# EE311_Example_Boost_Sch.net
KiCad netlist of a schematic drawn in Altium Designer
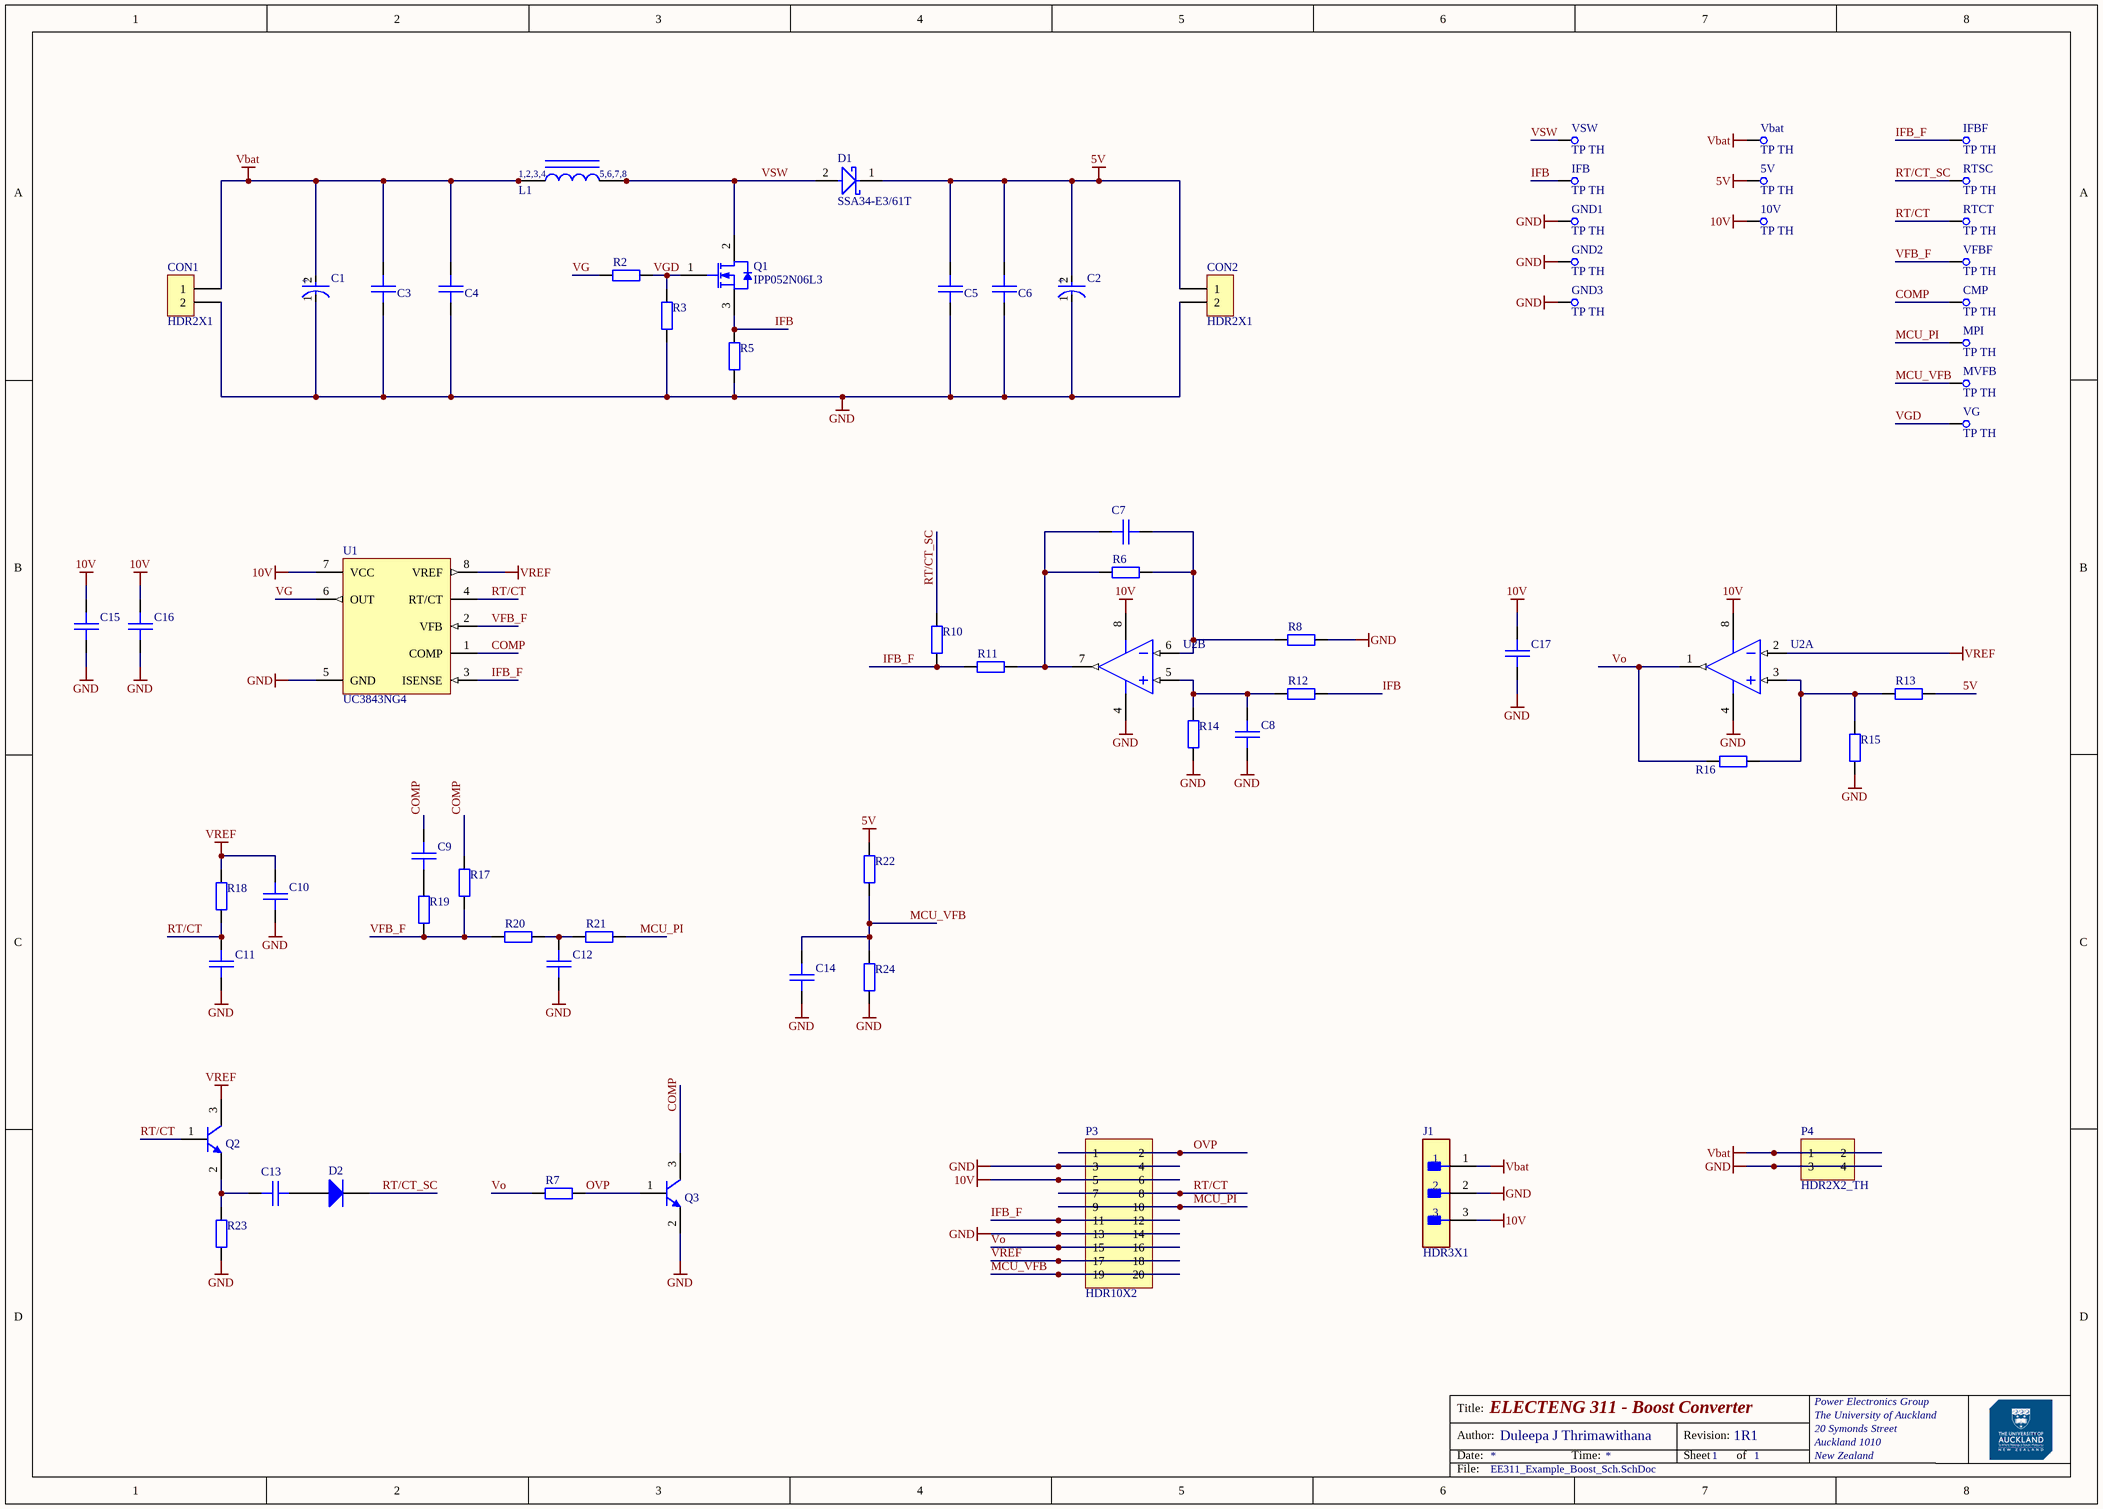
[diagram p0: EE311_Example_Boost_Sch.SchDoc]

(export (version "E")
  (design (tool "Eeschema 10.0.6"))
  (components
    (comp (ref "5V") (value "TP TH") (footprint "TP_TH_2.5mm") (libsource (lib "ECSE@UoA") (part "TP TH")))
    (comp (ref "10V") (value "TP TH") (footprint "TP_TH_2.5mm") (libsource (lib "ECSE@UoA") (part "TP TH")))
    (comp (ref "C1")
      (value "EEE-FK1K330P")
      (footprint "FP-FKF-MFG")
      (libsource (lib "ECSE@UoA") (part "a00bbbee19879c290e62620ae7e47b1"))
    )
    (comp (ref "C2")
      (value "EEE-FK1K330P")
      (footprint "FP-FKF-MFG")
      (libsource (lib "ECSE@UoA") (part "a00bbbee19879c290e62620ae7e47b1"))
    )
    (comp (ref "C3")
      (value "CCAP1210")
      (footprint "C1210")
      (description "Capacitor 1210")
      (libsource (lib "") (part "Symbol_2"))
    )
    (comp (ref "C4")
      (value "CCAP1210")
      (footprint "C1210")
      (description "Capacitor 1210")
      (libsource (lib "") (part "Symbol_2"))
    )
    (comp (ref "C5")
      (value "CCAP1210")
      (footprint "C1210")
      (description "Capacitor 1210")
      (libsource (lib "") (part "Symbol_2"))
    )
    (comp (ref "C6")
      (value "CCAP1210")
      (footprint "C1210")
      (description "Capacitor 1210")
      (libsource (lib "") (part "Symbol_2"))
    )
    (comp (ref "C7")
      (value "CCAP0805")
      (footprint "C0805")
      (description "Capacitor 0805")
      (libsource (lib "") (part "Symbol_2"))
    )
    (comp (ref "C8")
      (value "CCAP0805")
      (footprint "C0805")
      (description "Capacitor 0805")
      (libsource (lib "") (part "Symbol_2"))
    )
    (comp (ref "C9")
      (value "CCAP0805")
      (footprint "C0805")
      (description "Capacitor 0805")
      (libsource (lib "") (part "Symbol_2"))
    )
    (comp (ref "C10")
      (value "CCAP0805")
      (footprint "C0805")
      (description "Capacitor 0805")
      (libsource (lib "") (part "Symbol_2"))
    )
    (comp (ref "C11")
      (value "CCAP0805")
      (footprint "C0805")
      (description "Capacitor 0805")
      (libsource (lib "") (part "Symbol_2"))
    )
    (comp (ref "C12")
      (value "CCAP0805")
      (footprint "C0805")
      (description "Capacitor 0805")
      (libsource (lib "") (part "Symbol_2"))
    )
    (comp (ref "C13")
      (value "CCAP0805")
      (footprint "C0805")
      (description "Capacitor 0805")
      (libsource (lib "") (part "Symbol_2"))
    )
    (comp (ref "C14")
      (value "CCAP0805")
      (footprint "C0805")
      (description "Capacitor 0805")
      (libsource (lib "") (part "Symbol_2"))
    )
    (comp (ref "C15")
      (value "CCAP0805")
      (footprint "C0805")
      (description "Capacitor 0805")
      (libsource (lib "") (part "Symbol_2"))
    )
    (comp (ref "C16")
      (value "CCAP0805")
      (footprint "C0805")
      (description "Capacitor 0805")
      (libsource (lib "") (part "Symbol_2"))
    )
    (comp (ref "C17")
      (value "CCAP0805")
      (footprint "C0805")
      (description "Capacitor 0805")
      (libsource (lib "") (part "Symbol_2"))
    )
    (comp (ref "CMP") (value "TP TH") (footprint "TP_TH_2.5mm") (libsource (lib "ECSE@UoA") (part "TP TH")))
    (comp (ref "CON1")
      (value "HDR2X1")
      (footprint "HDR2X1_2P54")
      (description "Header 2X1")
      (libsource (lib "ECSE@UoA") (part "HDR2X1"))
    )
    (comp (ref "CON2")
      (value "HDR2X1")
      (footprint "HDR2X1_2P54")
      (description "Header 2X1")
      (libsource (lib "") (part "HDR2X1_1"))
    )
    (comp (ref "D1")
      (value "SSA34-E3/61T")
      (footprint "FP-95400-MFG")
      (description "Rectifier Diode, Schottky, 1 Phase, 1 Element, 3A, 40V V(RRM), Silicon, DO-214AC")
      (libsource (lib "ECSE@UoA") (part "1d6ec82d83fb6aee721767c19dac4b9"))
    )
    (comp (ref "D2")
      (value "1N4148_SMT_SOD123")
      (footprint "SOD123")
      (description "DIODE GEN PURP 100V 300MA SOD123")
      (fields
        (field (name "MANUFACTURER PART NUMBER") "1N4148W-13-F")
        (field (name "BASE PART NUMBER") "1N4148W")
      )
      (libsource (lib "ECSE@UoA") (part "1N4148_SMT_SOD123"))
    )
    (comp (ref "GND1") (value "TP TH") (footprint "TP_TH_3mm") (libsource (lib "ECSE@UoA") (part "TP TH")))
    (comp (ref "GND2") (value "TP TH") (footprint "TP_TH_3mm") (libsource (lib "ECSE@UoA") (part "TP TH")))
    (comp (ref "GND3") (value "TP TH") (footprint "TP_TH_3mm") (libsource (lib "ECSE@UoA") (part "TP TH")))
    (comp (ref "IFB") (value "TP TH") (footprint "TP_TH_3mm") (libsource (lib "ECSE@UoA") (part "TP TH")))
    (comp (ref "IFBF") (value "TP TH") (footprint "TP_TH_2.5mm") (libsource (lib "ECSE@UoA") (part "TP TH")))
    (comp (ref "J1")
      (value "HDR3X1")
      (footprint "FP-22-28-4035-MFG")
      (libsource (lib "ECSE@UoA") (part "0d3f023dd272f625e17a2be33dea85f"))
    )
    (comp (ref "L1")
      (value "Inductor EFD20")
      (footprint "EFD20")
      (description "Inductor with core")
      (libsource (lib "ECSE@UoA") (part "Inductor EFD20"))
    )
    (comp (ref "MPI") (value "TP TH") (footprint "TP_TH_2.5mm") (libsource (lib "ECSE@UoA") (part "TP TH")))
    (comp (ref "MVFB") (value "TP TH") (footprint "TP_TH_2.5mm") (libsource (lib "ECSE@UoA") (part "TP TH")))
    (comp (ref "P3")
      (value "HDR10X2")
      (footprint "HDR10X2_2P54")
      (description "Header, 10-Pin, Dual row")
      (libsource (lib "ECSE@UoA") (part "HDR10X2"))
    )
    (comp (ref "P4")
      (value "HDR2X2_TH")
      (footprint "HDR2X2_2P54_Male")
      (description "Male Header, 4-Pin, Dual row")
      (libsource (lib "ECSE@UoA") (part "HDR2X2"))
    )
    (comp (ref "Q1")
      (value "IPP052N06L3")
      (footprint "TO220VH")
      (fields (field (name "MANUFACTURER") "Infineon") (field (name "PARTNUMBER") "IPP052N06L3 G"))
      (libsource (lib "ECSE@UoA") (part "IPP052N06L3"))
    )
    (comp (ref "Q2")
      (value "MMBT2222A")
      (footprint "SOT23SM")
      (description "General Purpose Transistor, NPN Silicon, 3-Pin SOT-23, Pb-Free, Tape and Reel")
      (fields (field (name "PARTNUMBER") "MMBT2222ALT1G") (field (name "MANUFACTURER") "On Semiconductor"))
      (libsource (lib "ECSE@UoA") (part "MMBT2222A"))
    )
    (comp (ref "Q3")
      (value "MMBT2222A")
      (footprint "SOT23SM")
      (description "General Purpose Transistor, NPN Silicon, 3-Pin SOT-23, Pb-Free, Tape and Reel")
      (fields (field (name "PARTNUMBER") "MMBT2222ALT1G") (field (name "MANUFACTURER") "On Semiconductor"))
      (libsource (lib "ECSE@UoA") (part "MMBT2222A"))
    )
    (comp (ref "R2")
      (value "RES0805")
      (footprint "R0805")
      (description "Resistor 0805")
      (libsource (lib "ECSE@UoA") (part "Symbol"))
    )
    (comp (ref "R3")
      (value "RES0805")
      (footprint "R0805")
      (description "Resistor 0805")
      (libsource (lib "") (part "Symbol_1"))
    )
    (comp (ref "R5")
      (value "RES1210")
      (footprint "R1210")
      (description "Resistor 1210")
      (libsource (lib "") (part "Symbol_1"))
    )
    (comp (ref "R6")
      (value "RES0805")
      (footprint "R0805")
      (description "Resistor 0805")
      (libsource (lib "") (part "Symbol_1"))
    )
    (comp (ref "R7")
      (value "RES0805")
      (footprint "R0805")
      (description "Resistor 0805")
      (libsource (lib "") (part "Symbol_1"))
    )
    (comp (ref "R8")
      (value "RES0805")
      (footprint "R0805")
      (description "Resistor 0805")
      (libsource (lib "") (part "Symbol_1"))
    )
    (comp (ref "R10")
      (value "RES0805")
      (footprint "R0805")
      (description "Resistor 0805")
      (libsource (lib "") (part "Symbol_3"))
    )
    (comp (ref "R11")
      (value "RES0805")
      (footprint "R0805")
      (description "Resistor 0805")
      (libsource (lib "") (part "Symbol_1"))
    )
    (comp (ref "R12")
      (value "RES0805")
      (footprint "R0805")
      (description "Resistor 0805")
      (libsource (lib "") (part "Symbol_1"))
    )
    (comp (ref "R13")
      (value "RES0805")
      (footprint "R0805")
      (description "Resistor 0805")
      (libsource (lib "") (part "Symbol_1"))
    )
    (comp (ref "R14")
      (value "RES0805")
      (footprint "R0805")
      (description "Resistor 0805")
      (libsource (lib "ECSE@UoA") (part "Symbol"))
    )
    (comp (ref "R15")
      (value "RES0805")
      (footprint "R0805")
      (description "Resistor 0805")
      (libsource (lib "ECSE@UoA") (part "Symbol"))
    )
    (comp (ref "R16")
      (value "RES0805")
      (footprint "R0805")
      (description "Resistor 0805")
      (libsource (lib "") (part "Symbol_1"))
    )
    (comp (ref "R17")
      (value "RES0805")
      (footprint "R0805")
      (description "Resistor 0805")
      (libsource (lib "") (part "Symbol_1"))
    )
    (comp (ref "R18")
      (value "RES0805")
      (footprint "R0805")
      (description "Resistor 0805")
      (libsource (lib "") (part "Symbol_1"))
    )
    (comp (ref "R19")
      (value "RES0805")
      (footprint "R0805")
      (description "Resistor 0805")
      (libsource (lib "") (part "Symbol_1"))
    )
    (comp (ref "R20")
      (value "RES0805")
      (footprint "R0805")
      (description "Resistor 0805")
      (libsource (lib "") (part "Symbol_3"))
    )
    (comp (ref "R21")
      (value "RES0805")
      (footprint "R0805")
      (description "Resistor 0805")
      (libsource (lib "") (part "Symbol_3"))
    )
    (comp (ref "R22")
      (value "RES0805")
      (footprint "R0805")
      (description "Resistor 0805")
      (libsource (lib "") (part "Symbol_1"))
    )
    (comp (ref "R23")
      (value "RES0805")
      (footprint "R0805")
      (description "Resistor 0805")
      (libsource (lib "") (part "Symbol_3"))
    )
    (comp (ref "R24")
      (value "RES0805")
      (footprint "R0805")
      (description "Resistor 0805")
      (libsource (lib "") (part "Symbol_1"))
    )
    (comp (ref "RTCT") (value "TP TH") (footprint "TP_TH_2.5mm") (libsource (lib "ECSE@UoA") (part "TP TH")))
    (comp (ref "RTSC") (value "TP TH") (footprint "TP_TH_2.5mm") (libsource (lib "ECSE@UoA") (part "TP TH")))
    (comp (ref "U1")
      (value "UC3843NG4")
      (footprint "DIP-8")
      (libsource (lib "ECSE@UoA") (part "TI-UC3843P8"))
    )
    (comp (ref "U2")
      (value "LT6221")
      (footprint "SOIC8")
      (description "IC OPAMP LT6221 DUAL SM")
      (libsource (lib "ECSE@UoA") (part "LT6221"))
    )
    (comp (ref "Vbat") (value "TP TH") (footprint "TP_TH_2.5mm") (libsource (lib "ECSE@UoA") (part "TP TH")))
    (comp (ref "VFBF") (value "TP TH") (footprint "TP_TH_2.5mm") (libsource (lib "ECSE@UoA") (part "TP TH")))
    (comp (ref "VG") (value "TP TH") (footprint "TP_TH_2.5mm") (libsource (lib "ECSE@UoA") (part "TP TH")))
    (comp (ref "VSW") (value "TP TH") (footprint "TP_TH_3mm") (libsource (lib "ECSE@UoA") (part "TP TH")))
  )
  (nets
    (net (code "1") (name "/COMP") (class "Default")
      (node (ref "C9") (pin "1") (pinfunction "1_1") (pintype "passive"))
      (node (ref "CMP") (pin "1") (pinfunction "1_1") (pintype "passive"))
      (node (ref "Q3") (pin "3") (pinfunction "C_3") (pintype "passive"))
      (node (ref "R17") (pin "2") (pinfunction "2_2") (pintype "passive"))
      (node (ref "U1") (pin "1") (pinfunction "COMP_1") (pintype "passive"))
    )
    (net (code "2") (name "/IFB") (class "Default")
      (node (ref "IFB") (pin "1") (pinfunction "1_1") (pintype "passive"))
      (node (ref "Q1") (pin "3") (pinfunction "SOURCE_3") (pintype "passive"))
      (node (ref "R12") (pin "2") (pinfunction "2_2") (pintype "passive"))
      (node (ref "R5") (pin "2") (pinfunction "2_2") (pintype "passive"))
    )
    (net (code "3") (name "/IFB_F") (class "Default")
      (node (ref "IFBF") (pin "1") (pinfunction "1_1") (pintype "passive"))
      (node (ref "P3") (pin "11") (pinfunction "11_11") (pintype "passive"))
      (node (ref "P3") (pin "12") (pinfunction "12_12") (pintype "passive"))
      (node (ref "R10") (pin "2") (pinfunction "2_2") (pintype "passive"))
      (node (ref "R11") (pin "1") (pinfunction "1_1") (pintype "passive"))
      (node (ref "U1") (pin "3") (pinfunction "ISENSE_3") (pintype "input"))
    )
    (net (code "4") (name "/MCU_PI") (class "Default")
      (node (ref "MPI") (pin "1") (pinfunction "1_1") (pintype "passive"))
      (node (ref "P3") (pin "10") (pinfunction "10_10") (pintype "passive"))
      (node (ref "P3") (pin "9") (pinfunction "9_9") (pintype "passive"))
      (node (ref "R21") (pin "1") (pinfunction "1_1") (pintype "passive"))
    )
    (net (code "5") (name "/MCU_VFB") (class "Default")
      (node (ref "C14") (pin "1") (pinfunction "1_1") (pintype "passive"))
      (node (ref "MVFB") (pin "1") (pinfunction "1_1") (pintype "passive"))
      (node (ref "P3") (pin "19") (pinfunction "19_19") (pintype "passive"))
      (node (ref "P3") (pin "20") (pinfunction "20_20") (pintype "passive"))
      (node (ref "R22") (pin "1") (pinfunction "1_1") (pintype "passive"))
      (node (ref "R24") (pin "2") (pinfunction "2_2") (pintype "passive"))
    )
    (net (code "6") (name "/OVP") (class "Default")
      (node (ref "P3") (pin "1") (pinfunction "1_1") (pintype "passive"))
      (node (ref "P3") (pin "2") (pinfunction "2_2") (pintype "passive"))
      (node (ref "Q3") (pin "1") (pinfunction "B_1") (pintype "passive"))
      (node (ref "R7") (pin "2") (pinfunction "2_2") (pintype "passive"))
    )
    (net (code "7") (name "/RT{slash}CT") (class "Default")
      (node (ref "C11") (pin "1") (pinfunction "1_1") (pintype "passive"))
      (node (ref "P3") (pin "7") (pinfunction "7_7") (pintype "passive"))
      (node (ref "P3") (pin "8") (pinfunction "8_8") (pintype "passive"))
      (node (ref "Q2") (pin "1") (pinfunction "B_1") (pintype "passive"))
      (node (ref "R18") (pin "1") (pinfunction "1_1") (pintype "passive"))
      (node (ref "RTCT") (pin "1") (pinfunction "1_1") (pintype "passive"))
      (node (ref "U1") (pin "4") (pinfunction "RT/CT_4") (pintype "passive"))
    )
    (net (code "8") (name "/RT{slash}CT_SC") (class "Default")
      (node (ref "D2") (pin "2") (pinfunction "K_2") (pintype "passive"))
      (node (ref "R10") (pin "1") (pinfunction "1_1") (pintype "passive"))
      (node (ref "RTSC") (pin "1") (pinfunction "1_1") (pintype "passive"))
    )
    (net (code "9") (name "/VFB_F") (class "Default")
      (node (ref "R17") (pin "1") (pinfunction "1_1") (pintype "passive"))
      (node (ref "R19") (pin "1") (pinfunction "1_1") (pintype "passive"))
      (node (ref "R20") (pin "2") (pinfunction "2_2") (pintype "passive"))
      (node (ref "U1") (pin "2") (pinfunction "VFB_2") (pintype "input"))
      (node (ref "VFBF") (pin "1") (pinfunction "1_1") (pintype "passive"))
    )
    (net (code "10") (name "/VG") (class "Default")
      (node (ref "R2") (pin "1") (pinfunction "1_1") (pintype "passive"))
      (node (ref "U1") (pin "6") (pinfunction "OUT_6") (pintype "output"))
    )
    (net (code "11") (name "/VGD") (class "Default")
      (node (ref "Q1") (pin "1") (pinfunction "GATE_1") (pintype "passive"))
      (node (ref "R2") (pin "2") (pinfunction "2_2") (pintype "passive"))
      (node (ref "R3") (pin "2") (pinfunction "2_2") (pintype "passive"))
      (node (ref "VG") (pin "1") (pinfunction "1_1") (pintype "passive"))
    )
    (net (code "12") (name "/VSW") (class "Default")
      (node (ref "D1") (pin "2") (pinfunction "A_2") (pintype "passive"))
      (node (ref "L1") (pin "5") (pinfunction "5_5") (pintype "passive"))
      (node (ref "L1") (pin "6") (pinfunction "6_6") (pintype "passive"))
      (node (ref "L1") (pin "7") (pinfunction "7_7") (pintype "passive"))
      (node (ref "L1") (pin "8") (pinfunction "8_8") (pintype "passive"))
      (node (ref "Q1") (pin "2") (pinfunction "DRAIN_2") (pintype "passive"))
      (node (ref "VSW") (pin "1") (pinfunction "1_1") (pintype "passive"))
    )
    (net (code "13") (name "/Vo") (class "Default")
      (node (ref "P3") (pin "15") (pinfunction "15_15") (pintype "passive"))
      (node (ref "P3") (pin "16") (pinfunction "16_16") (pintype "passive"))
      (node (ref "R16") (pin "1") (pinfunction "1_1") (pintype "passive"))
      (node (ref "R7") (pin "1") (pinfunction "1_1") (pintype "passive"))
      (node (ref "U2") (pin "1") (pinfunction "OUT1_1") (pintype "output"))
    )
    (net (code "14") (name "5V") (class "Default")
      (node (ref "5V") (pin "1") (pinfunction "1_1") (pintype "passive"))
      (node (ref "C2") (pin "2") (pinfunction "A_2") (pintype "passive"))
      (node (ref "C5") (pin "2") (pinfunction "2_2") (pintype "passive"))
      (node (ref "C6") (pin "2") (pinfunction "2_2") (pintype "passive"))
      (node (ref "CON2") (pin "1") (pinfunction "1_1") (pintype "passive"))
      (node (ref "D1") (pin "1") (pinfunction "C_1") (pintype "passive"))
      (node (ref "R13") (pin "2") (pinfunction "2_2") (pintype "passive"))
      (node (ref "R22") (pin "2") (pinfunction "2_2") (pintype "passive"))
    )
    (net (code "15") (name "10V") (class "Default")
      (node (ref "10V") (pin "1") (pinfunction "1_1") (pintype "passive"))
      (node (ref "C15") (pin "1") (pinfunction "1_1") (pintype "passive"))
      (node (ref "C16") (pin "1") (pinfunction "1_1") (pintype "passive"))
      (node (ref "C17") (pin "1") (pinfunction "1_1") (pintype "passive"))
      (node (ref "J1") (pin "3") (pinfunction "3_3") (pintype "passive"))
      (node (ref "P3") (pin "5") (pinfunction "5_5") (pintype "passive"))
      (node (ref "P3") (pin "6") (pinfunction "6_6") (pintype "passive"))
      (node (ref "U1") (pin "7") (pinfunction "VCC_7") (pintype "power_in"))
      (node (ref "U2") (pin "8") (pinfunction "VDD_8") (pintype "power_in"))
    )
    (net (code "16") (name "GND") (class "Default")
      (node (ref "C1") (pin "1") (pinfunction "C_1") (pintype "passive"))
      (node (ref "C10") (pin "2") (pinfunction "2_2") (pintype "passive"))
      (node (ref "C11") (pin "2") (pinfunction "2_2") (pintype "passive"))
      (node (ref "C12") (pin "2") (pinfunction "2_2") (pintype "passive"))
      (node (ref "C14") (pin "2") (pinfunction "2_2") (pintype "passive"))
      (node (ref "C15") (pin "2") (pinfunction "2_2") (pintype "passive"))
      (node (ref "C16") (pin "2") (pinfunction "2_2") (pintype "passive"))
      (node (ref "C17") (pin "2") (pinfunction "2_2") (pintype "passive"))
      (node (ref "C2") (pin "1") (pinfunction "C_1") (pintype "passive"))
      (node (ref "C3") (pin "1") (pinfunction "1_1") (pintype "passive"))
      (node (ref "C4") (pin "1") (pinfunction "1_1") (pintype "passive"))
      (node (ref "C5") (pin "1") (pinfunction "1_1") (pintype "passive"))
      (node (ref "C6") (pin "1") (pinfunction "1_1") (pintype "passive"))
      (node (ref "C8") (pin "2") (pinfunction "2_2") (pintype "passive"))
      (node (ref "CON1") (pin "2") (pinfunction "2_2") (pintype "passive"))
      (node (ref "CON2") (pin "2") (pinfunction "2_2") (pintype "passive"))
      (node (ref "GND1") (pin "1") (pinfunction "1_1") (pintype "passive"))
      (node (ref "GND2") (pin "1") (pinfunction "1_1") (pintype "passive"))
      (node (ref "GND3") (pin "1") (pinfunction "1_1") (pintype "passive"))
      (node (ref "J1") (pin "2") (pinfunction "2_2") (pintype "passive"))
      (node (ref "P3") (pin "13") (pinfunction "13_13") (pintype "passive"))
      (node (ref "P3") (pin "14") (pinfunction "14_14") (pintype "passive"))
      (node (ref "P3") (pin "3") (pinfunction "3_3") (pintype "passive"))
      (node (ref "P3") (pin "4") (pinfunction "4_4") (pintype "passive"))
      (node (ref "P4") (pin "3") (pinfunction "3_3") (pintype "passive"))
      (node (ref "P4") (pin "4") (pinfunction "4_4") (pintype "passive"))
      (node (ref "Q3") (pin "2") (pinfunction "E_2") (pintype "passive"))
      (node (ref "R14") (pin "1") (pinfunction "1_1") (pintype "passive"))
      (node (ref "R15") (pin "1") (pinfunction "1_1") (pintype "passive"))
      (node (ref "R23") (pin "2") (pinfunction "2_2") (pintype "passive"))
      (node (ref "R24") (pin "1") (pinfunction "1_1") (pintype "passive"))
      (node (ref "R3") (pin "1") (pinfunction "1_1") (pintype "passive"))
      (node (ref "R5") (pin "1") (pinfunction "1_1") (pintype "passive"))
      (node (ref "R8") (pin "2") (pinfunction "2_2") (pintype "passive"))
      (node (ref "U1") (pin "5") (pinfunction "GND_5") (pintype "power_in"))
      (node (ref "U2") (pin "4") (pinfunction "GND_4") (pintype "power_in"))
    )
    (net (code "17") (name "Net-(C9-Pad2)") (class "Default")
      (node (ref "C9") (pin "2") (pinfunction "2_2") (pintype "passive"))
      (node (ref "R19") (pin "2") (pinfunction "2_2") (pintype "passive"))
    )
    (net (code "18") (name "Net-(C12-Pad1)") (class "Default")
      (node (ref "C12") (pin "1") (pinfunction "1_1") (pintype "passive"))
      (node (ref "R20") (pin "1") (pinfunction "1_1") (pintype "passive"))
      (node (ref "R21") (pin "2") (pinfunction "2_2") (pintype "passive"))
    )
    (net (code "19") (name "Net-(D2-A)") (class "Default")
      (node (ref "C13") (pin "2") (pinfunction "2_2") (pintype "passive"))
      (node (ref "D2") (pin "1") (pinfunction "A_1") (pintype "passive"))
    )
    (net (code "20") (name "Net-(Q2-E)") (class "Default")
      (node (ref "C13") (pin "1") (pinfunction "1_1") (pintype "passive"))
      (node (ref "Q2") (pin "2") (pinfunction "E_2") (pintype "passive"))
      (node (ref "R23") (pin "1") (pinfunction "1_1") (pintype "passive"))
    )
    (net (code "21") (name "Net-(U2A-IN1+)") (class "Default")
      (node (ref "R13") (pin "1") (pinfunction "1_1") (pintype "passive"))
      (node (ref "R15") (pin "2") (pinfunction "2_2") (pintype "passive"))
      (node (ref "R16") (pin "2") (pinfunction "2_2") (pintype "passive"))
      (node (ref "U2") (pin "3") (pinfunction "IN1+_3") (pintype "input"))
    )
    (net (code "22") (name "Net-(U2B-IN1+)") (class "Default")
      (node (ref "C8") (pin "1") (pinfunction "1_1") (pintype "passive"))
      (node (ref "R12") (pin "1") (pinfunction "1_1") (pintype "passive"))
      (node (ref "R14") (pin "2") (pinfunction "2_2") (pintype "passive"))
      (node (ref "U2") (pin "5") (pinfunction "IN1+_5") (pintype "input"))
    )
    (net (code "23") (name "Net-(U2B-IN1-)") (class "Default")
      (node (ref "C7") (pin "2") (pinfunction "2_2") (pintype "passive"))
      (node (ref "R6") (pin "2") (pinfunction "2_2") (pintype "passive"))
      (node (ref "R8") (pin "1") (pinfunction "1_1") (pintype "passive"))
      (node (ref "U2") (pin "6") (pinfunction "IN1-_6") (pintype "input"))
    )
    (net (code "24") (name "Net-(U2B-OUT1)") (class "Default")
      (node (ref "C7") (pin "1") (pinfunction "1_1") (pintype "passive"))
      (node (ref "R11") (pin "2") (pinfunction "2_2") (pintype "passive"))
      (node (ref "R6") (pin "1") (pinfunction "1_1") (pintype "passive"))
      (node (ref "U2") (pin "7") (pinfunction "OUT1_7") (pintype "output"))
    )
    (net (code "25") (name "VREF") (class "Default")
      (node (ref "C10") (pin "1") (pinfunction "1_1") (pintype "passive"))
      (node (ref "P3") (pin "17") (pinfunction "17_17") (pintype "passive"))
      (node (ref "P3") (pin "18") (pinfunction "18_18") (pintype "passive"))
      (node (ref "Q2") (pin "3") (pinfunction "C_3") (pintype "passive"))
      (node (ref "R18") (pin "2") (pinfunction "2_2") (pintype "passive"))
      (node (ref "U1") (pin "8") (pinfunction "VREF_8") (pintype "output"))
      (node (ref "U2") (pin "2") (pinfunction "IN1-_2") (pintype "input"))
    )
    (net (code "26") (name "Vbat") (class "Default")
      (node (ref "C1") (pin "2") (pinfunction "A_2") (pintype "passive"))
      (node (ref "C3") (pin "2") (pinfunction "2_2") (pintype "passive"))
      (node (ref "C4") (pin "2") (pinfunction "2_2") (pintype "passive"))
      (node (ref "CON1") (pin "1") (pinfunction "1_1") (pintype "passive"))
      (node (ref "J1") (pin "1") (pinfunction "1_1") (pintype "passive"))
      (node (ref "L1") (pin "1") (pinfunction "1_1") (pintype "passive"))
      (node (ref "L1") (pin "2") (pinfunction "2_2") (pintype "passive"))
      (node (ref "L1") (pin "3") (pinfunction "3_3") (pintype "passive"))
      (node (ref "L1") (pin "4") (pinfunction "4_4") (pintype "passive"))
      (node (ref "P4") (pin "1") (pinfunction "1_1") (pintype "passive"))
      (node (ref "P4") (pin "2") (pinfunction "2_2") (pintype "passive"))
      (node (ref "Vbat") (pin "1") (pinfunction "1_1") (pintype "passive"))
    )
  )
)
